# followLineMain.net
KiCad netlist of a schematic drawn in EAGLE
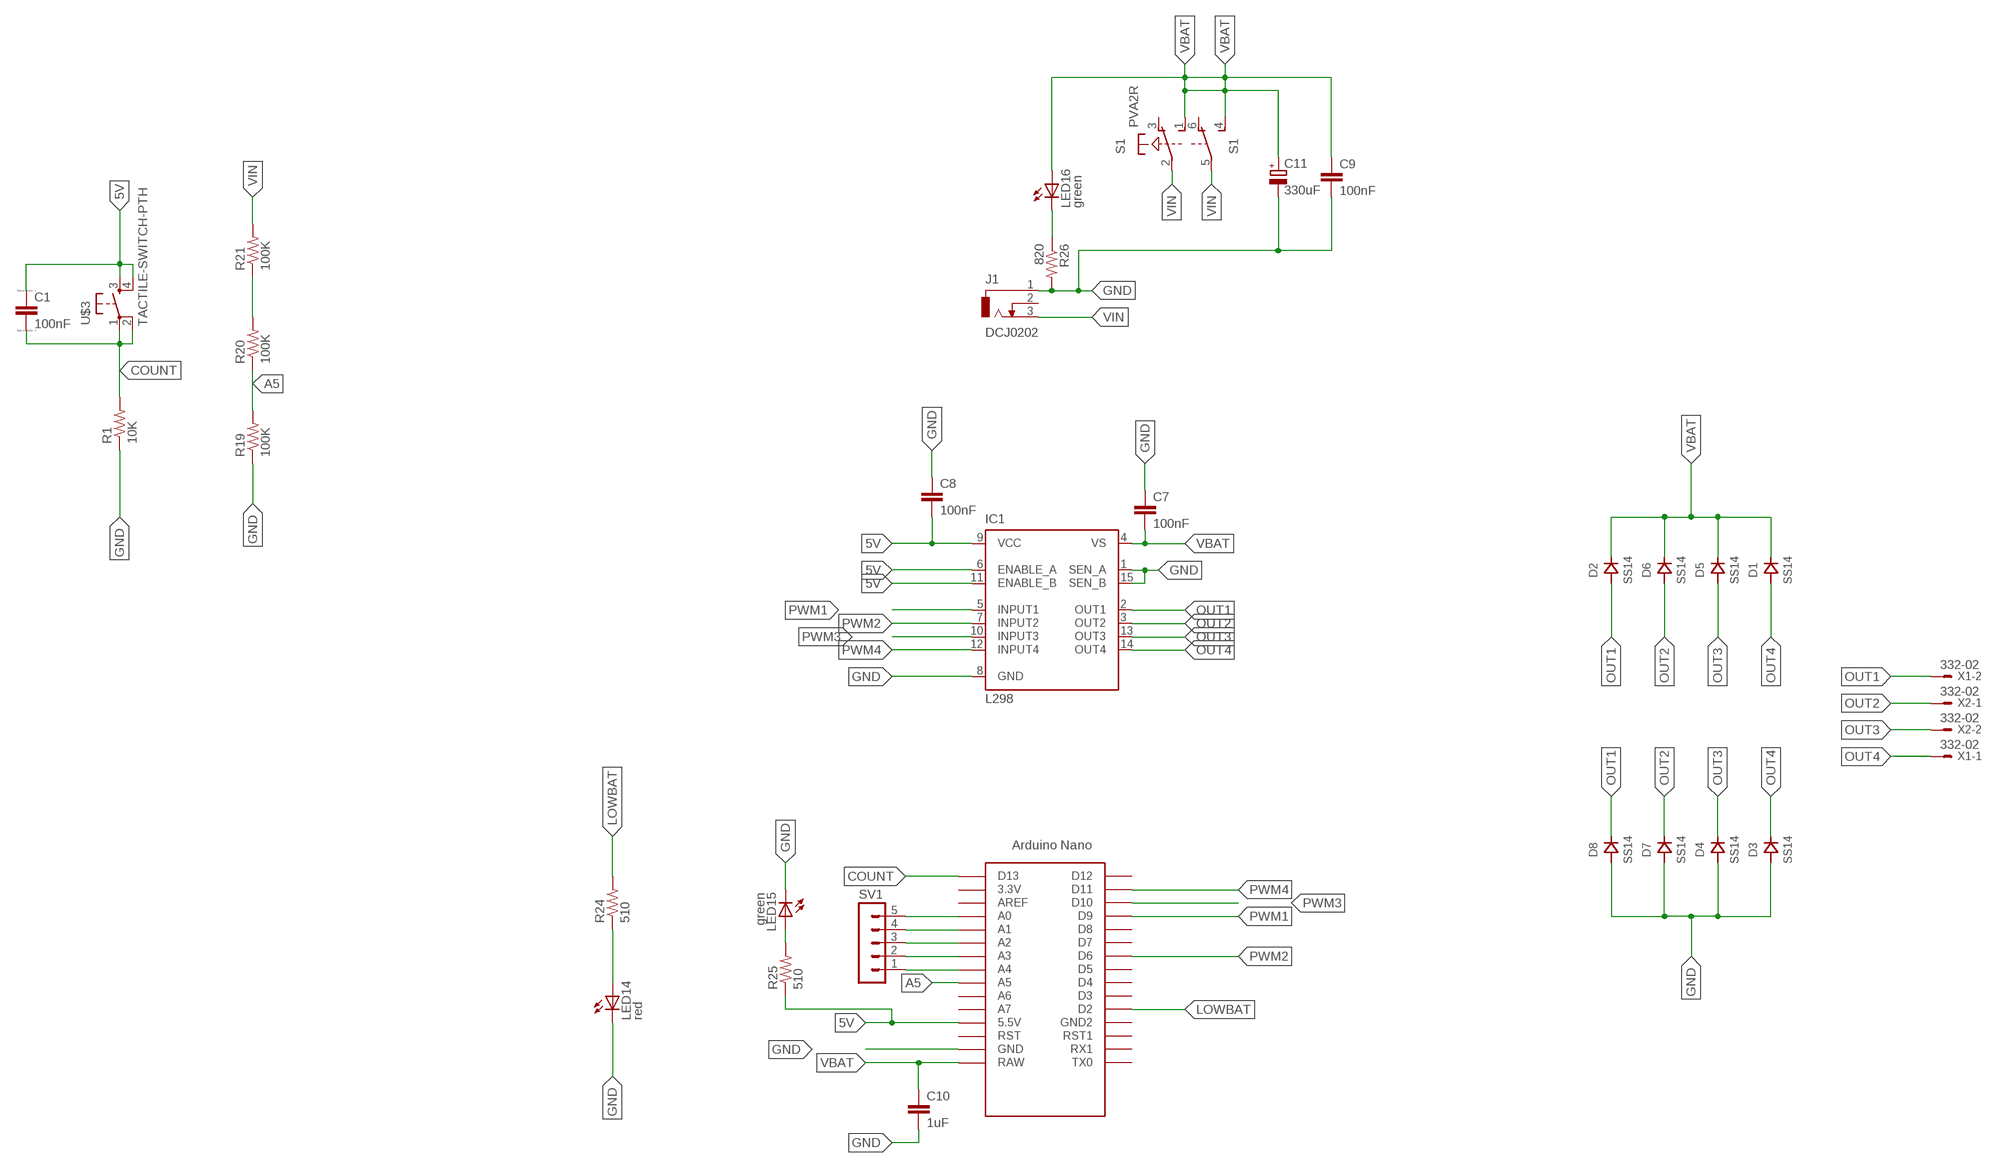
[diagram p0: schematic, sheet 1]

(export (version "E")
  (design (tool "Eeschema 10.0.6"))
  (components
    (comp (ref "C1")
      (value "100nF")
      (footprint "eagle-import:C0603")
      (libsource (lib "eagle-import") (part "CC0603"))
    )
    (comp (ref "C7")
      (value "100nF")
      (footprint "eagle-import:0805")
      (libsource (lib "eagle-import") (part "CAP0805"))
    )
    (comp (ref "C8")
      (value "100nF")
      (footprint "eagle-import:0805")
      (libsource (lib "eagle-import") (part "CAP0805"))
    )
    (comp (ref "C9")
      (value "100nF")
      (footprint "eagle-import:0805")
      (libsource (lib "eagle-import") (part "CAP0805"))
    )
    (comp (ref "C10")
      (value "1uF")
      (footprint "eagle-import:1206")
      (libsource (lib "eagle-import") (part "CAP1206"))
    )
    (comp (ref "C11")
      (value "330uF")
      (footprint "eagle-import:E5-13")
      (libsource (lib "eagle-import") (part "CPOL-EUE5-13"))
    )
    (comp (ref "D1")
      (value "SS14")
      (footprint "eagle-import:DO214")
      (libsource (lib "eagle-import") (part "SS14"))
    )
    (comp (ref "D2")
      (value "SS14")
      (footprint "eagle-import:DO214")
      (libsource (lib "eagle-import") (part "SS14"))
    )
    (comp (ref "D3")
      (value "SS14")
      (footprint "eagle-import:DO214")
      (libsource (lib "eagle-import") (part "SS14"))
    )
    (comp (ref "D4")
      (value "SS14")
      (footprint "eagle-import:DO214")
      (libsource (lib "eagle-import") (part "SS14"))
    )
    (comp (ref "D5")
      (value "SS14")
      (footprint "eagle-import:DO214")
      (libsource (lib "eagle-import") (part "SS14"))
    )
    (comp (ref "D6")
      (value "SS14")
      (footprint "eagle-import:DO214")
      (libsource (lib "eagle-import") (part "SS14"))
    )
    (comp (ref "D7")
      (value "SS14")
      (footprint "eagle-import:DO214")
      (libsource (lib "eagle-import") (part "SS14"))
    )
    (comp (ref "D8")
      (value "SS14")
      (footprint "eagle-import:DO214")
      (libsource (lib "eagle-import") (part "SS14"))
    )
    (comp (ref "IC1")
      (value "L298")
      (footprint "eagle-import:MULTIWATT-15")
      (fields (field (name "MPN") "L298N"))
      (libsource (lib "eagle-import") (part "L298"))
    )
    (comp (ref "J1")
      (value "DCJ0202")
      (footprint "eagle-import:DCJ0202")
      (libsource (lib "eagle-import") (part "DCJ0202"))
    )
    (comp (ref "LED14")
      (value "red")
      (footprint "eagle-import:SML0805")
      (libsource (lib "eagle-import") (part "LEDSML0805"))
    )
    (comp (ref "LED15")
      (value "green")
      (footprint "eagle-import:SML0805")
      (libsource (lib "eagle-import") (part "LEDSML0805"))
    )
    (comp (ref "LED16")
      (value "green")
      (footprint "eagle-import:SML0805")
      (libsource (lib "eagle-import") (part "LEDSML0805"))
    )
    (comp (ref "R1")
      (value "10K")
      (footprint "eagle-import:0805")
      (libsource (lib "eagle-import") (part "RESISTOR0805-RES"))
    )
    (comp (ref "R19")
      (value "100K")
      (footprint "eagle-import:0805")
      (libsource (lib "eagle-import") (part "RESISTOR0805-RES"))
    )
    (comp (ref "R20")
      (value "100K")
      (footprint "eagle-import:0805")
      (libsource (lib "eagle-import") (part "RESISTOR0805-RES"))
    )
    (comp (ref "R21")
      (value "100K")
      (footprint "eagle-import:0805")
      (libsource (lib "eagle-import") (part "RESISTOR0805-RES"))
    )
    (comp (ref "R24")
      (value "510")
      (footprint "eagle-import:0805")
      (libsource (lib "eagle-import") (part "RESISTOR0805-RES"))
    )
    (comp (ref "R25")
      (value "510")
      (footprint "eagle-import:0805")
      (libsource (lib "eagle-import") (part "RESISTOR0805-RES"))
    )
    (comp (ref "R26")
      (value "820")
      (footprint "eagle-import:0805")
      (libsource (lib "eagle-import") (part "RESISTOR0805-RES"))
    )
    (comp (ref "S1")
      (value "PVA2R")
      (footprint "eagle-import:PVA2R")
      (libsource (lib "eagle-import") (part "PVA2R"))
    )
    (comp (ref "SV1")
      (value "MA05-1")
      (footprint "eagle-import:MA05-1")
      (libsource (lib "eagle-import") (part "MA05-1"))
    )
    (comp (ref "U$1")
      (value "NANO")
      (footprint "eagle-import:NANO")
      (libsource (lib "eagle-import") (part "NANO"))
    )
    (comp (ref "U$3")
      (value "TACTILE-SWITCH-PTH")
      (footprint "eagle-import:TAC-SWITCH-PTH")
      (libsource (lib "eagle-import") (part "TACTILE-SWITCH-PTH"))
    )
    (comp (ref "X1")
      (value "332-02")
      (footprint "eagle-import:332-02")
      (libsource (lib "eagle-import") (part "332-02"))
    )
    (comp (ref "X2")
      (value "332-02")
      (footprint "eagle-import:332-02")
      (libsource (lib "eagle-import") (part "332-02"))
    )
  )
  (nets
    (net (code "1") (name "5V") (class "Default")
      (node (ref "C1") (pin "1") (pinfunction "1_1") (pintype "passive"))
      (node (ref "C8") (pin "2") (pinfunction "2_2") (pintype "passive"))
      (node (ref "IC1") (pin "11") (pinfunction "ENABLE_B_11") (pintype "input"))
      (node (ref "IC1") (pin "6") (pinfunction "ENABLE_A_6") (pintype "input"))
      (node (ref "IC1") (pin "9") (pinfunction "VCC_9") (pintype "power_in"))
      (node (ref "R25") (pin "1") (pinfunction "1_1") (pintype "passive"))
      (node (ref "U$1") (pin "5V") (pinfunction "5.5V_5V") (pintype "bidirectional"))
      (node (ref "U$3") (pin "3") (pinfunction "3_3") (pintype "passive"))
      (node (ref "U$3") (pin "4") (pinfunction "4_4") (pintype "passive"))
    )
    (net (code "2") (name "A5") (class "Default")
      (node (ref "R19") (pin "2") (pinfunction "2_2") (pintype "passive"))
      (node (ref "R20") (pin "1") (pinfunction "1_1") (pintype "passive"))
      (node (ref "U$1") (pin "A5") (pinfunction "A5_A5") (pintype "bidirectional"))
    )
    (net (code "3") (name "COUNT") (class "Default")
      (node (ref "C1") (pin "2") (pinfunction "2_2") (pintype "passive"))
      (node (ref "R1") (pin "2") (pinfunction "2_2") (pintype "passive"))
      (node (ref "U$1") (pin "D13") (pinfunction "D13_D13") (pintype "bidirectional"))
      (node (ref "U$3") (pin "1") (pinfunction "1_1") (pintype "passive"))
      (node (ref "U$3") (pin "2") (pinfunction "2_2") (pintype "passive"))
    )
    (net (code "4") (name "GND") (class "Default")
      (node (ref "C10") (pin "2") (pinfunction "2_2") (pintype "passive"))
      (node (ref "C11") (pin "-") (pinfunction "-_-") (pintype "passive"))
      (node (ref "C7") (pin "1") (pinfunction "1_1") (pintype "passive"))
      (node (ref "C8") (pin "1") (pinfunction "1_1") (pintype "passive"))
      (node (ref "C9") (pin "2") (pinfunction "2_2") (pintype "passive"))
      (node (ref "D3") (pin "ANODE") (pinfunction "ANODE_ANODE") (pintype "bidirectional"))
      (node (ref "D4") (pin "ANODE") (pinfunction "ANODE_ANODE") (pintype "bidirectional"))
      (node (ref "D7") (pin "ANODE") (pinfunction "ANODE_ANODE") (pintype "bidirectional"))
      (node (ref "D8") (pin "ANODE") (pinfunction "ANODE_ANODE") (pintype "bidirectional"))
      (node (ref "IC1") (pin "1") (pinfunction "SEN_A_1") (pintype "input"))
      (node (ref "IC1") (pin "15") (pinfunction "SEN_B_15") (pintype "input"))
      (node (ref "IC1") (pin "8") (pinfunction "GND_8") (pintype "power_in"))
      (node (ref "J1") (pin "1") (pinfunction "1_1") (pintype "passive"))
      (node (ref "LED14") (pin "C") (pinfunction "C_C") (pintype "passive"))
      (node (ref "LED15") (pin "C") (pinfunction "C_C") (pintype "passive"))
      (node (ref "R1") (pin "1") (pinfunction "1_1") (pintype "passive"))
      (node (ref "R19") (pin "1") (pinfunction "1_1") (pintype "passive"))
      (node (ref "R26") (pin "2") (pinfunction "2_2") (pintype "passive"))
      (node (ref "U$1") (pin "GND") (pinfunction "GND_GND") (pintype "bidirectional"))
    )
    (net (code "5") (name "LOWBAT") (class "Default")
      (node (ref "R24") (pin "2") (pinfunction "2_2") (pintype "passive"))
      (node (ref "U$1") (pin "D2") (pinfunction "D2_D2") (pintype "bidirectional"))
    )
    (net (code "6") (name "Net-(LED14-PadA)") (class "Default")
      (node (ref "LED14") (pin "A") (pinfunction "A_A") (pintype "passive"))
      (node (ref "R24") (pin "1") (pinfunction "1_1") (pintype "passive"))
    )
    (net (code "7") (name "Net-(LED15-PadA)") (class "Default")
      (node (ref "LED15") (pin "A") (pinfunction "A_A") (pintype "passive"))
      (node (ref "R25") (pin "2") (pinfunction "2_2") (pintype "passive"))
    )
    (net (code "8") (name "Net-(LED16-PadC)") (class "Default")
      (node (ref "LED16") (pin "C") (pinfunction "C_C") (pintype "passive"))
      (node (ref "R26") (pin "1") (pinfunction "1_1") (pintype "passive"))
    )
    (net (code "9") (name "Net-(R20-Pad2)") (class "Default")
      (node (ref "R20") (pin "2") (pinfunction "2_2") (pintype "passive"))
      (node (ref "R21") (pin "1") (pinfunction "1_1") (pintype "passive"))
    )
    (net (code "10") (name "Net-(SV1-Pad1)") (class "Default")
      (node (ref "SV1") (pin "1") (pinfunction "1_1") (pintype "passive"))
      (node (ref "U$1") (pin "A4") (pinfunction "A4_A4") (pintype "bidirectional"))
    )
    (net (code "11") (name "Net-(SV1-Pad2)") (class "Default")
      (node (ref "SV1") (pin "2") (pinfunction "2_2") (pintype "passive"))
      (node (ref "U$1") (pin "A3") (pinfunction "A3_A3") (pintype "bidirectional"))
    )
    (net (code "12") (name "Net-(SV1-Pad3)") (class "Default")
      (node (ref "SV1") (pin "3") (pinfunction "3_3") (pintype "passive"))
      (node (ref "U$1") (pin "A2") (pinfunction "A2_A2") (pintype "bidirectional"))
    )
    (net (code "13") (name "Net-(SV1-Pad4)") (class "Default")
      (node (ref "SV1") (pin "4") (pinfunction "4_4") (pintype "passive"))
      (node (ref "U$1") (pin "A1") (pinfunction "A1_A1") (pintype "bidirectional"))
    )
    (net (code "14") (name "Net-(SV1-Pad5)") (class "Default")
      (node (ref "SV1") (pin "5") (pinfunction "5_5") (pintype "passive"))
      (node (ref "U$1") (pin "A0") (pinfunction "A0_A0") (pintype "bidirectional"))
    )
    (net (code "15") (name "OUT1") (class "Default")
      (node (ref "D2") (pin "ANODE") (pinfunction "ANODE_ANODE") (pintype "bidirectional"))
      (node (ref "D8") (pin "CATHODE") (pinfunction "CATHODE_CATHODE") (pintype "bidirectional"))
      (node (ref "IC1") (pin "2") (pinfunction "OUT1_2") (pintype "output"))
      (node (ref "X1") (pin "2") (pinfunction "S_2") (pintype "passive"))
    )
    (net (code "16") (name "OUT2") (class "Default")
      (node (ref "D6") (pin "ANODE") (pinfunction "ANODE_ANODE") (pintype "bidirectional"))
      (node (ref "D7") (pin "CATHODE") (pinfunction "CATHODE_CATHODE") (pintype "bidirectional"))
      (node (ref "IC1") (pin "3") (pinfunction "OUT2_3") (pintype "output"))
      (node (ref "X2") (pin "1") (pinfunction "S_1") (pintype "passive"))
    )
    (net (code "17") (name "OUT3") (class "Default")
      (node (ref "D4") (pin "CATHODE") (pinfunction "CATHODE_CATHODE") (pintype "bidirectional"))
      (node (ref "D5") (pin "ANODE") (pinfunction "ANODE_ANODE") (pintype "bidirectional"))
      (node (ref "IC1") (pin "13") (pinfunction "OUT3_13") (pintype "output"))
      (node (ref "X2") (pin "2") (pinfunction "S_2") (pintype "passive"))
    )
    (net (code "18") (name "OUT4") (class "Default")
      (node (ref "D1") (pin "ANODE") (pinfunction "ANODE_ANODE") (pintype "bidirectional"))
      (node (ref "D3") (pin "CATHODE") (pinfunction "CATHODE_CATHODE") (pintype "bidirectional"))
      (node (ref "IC1") (pin "14") (pinfunction "OUT4_14") (pintype "output"))
      (node (ref "X1") (pin "1") (pinfunction "S_1") (pintype "passive"))
    )
    (net (code "19") (name "PWM1") (class "Default")
      (node (ref "IC1") (pin "5") (pinfunction "INPUT1_5") (pintype "input"))
      (node (ref "U$1") (pin "D9") (pinfunction "D9_D9") (pintype "bidirectional"))
    )
    (net (code "20") (name "PWM2") (class "Default")
      (node (ref "IC1") (pin "7") (pinfunction "INPUT2_7") (pintype "input"))
      (node (ref "U$1") (pin "D6") (pinfunction "D6_D6") (pintype "bidirectional"))
    )
    (net (code "21") (name "PWM3") (class "Default")
      (node (ref "IC1") (pin "10") (pinfunction "INPUT3_10") (pintype "input"))
      (node (ref "U$1") (pin "D10") (pinfunction "D10_D10") (pintype "bidirectional"))
    )
    (net (code "22") (name "PWM4") (class "Default")
      (node (ref "IC1") (pin "12") (pinfunction "INPUT4_12") (pintype "input"))
      (node (ref "U$1") (pin "D11") (pinfunction "D11_D11") (pintype "bidirectional"))
    )
    (net (code "23") (name "VBAT") (class "Default")
      (node (ref "C10") (pin "1") (pinfunction "1_1") (pintype "passive"))
      (node (ref "C11") (pin "+") (pinfunction "+_+") (pintype "passive"))
      (node (ref "C7") (pin "2") (pinfunction "2_2") (pintype "passive"))
      (node (ref "C9") (pin "1") (pinfunction "1_1") (pintype "passive"))
      (node (ref "D1") (pin "CATHODE") (pinfunction "CATHODE_CATHODE") (pintype "bidirectional"))
      (node (ref "D2") (pin "CATHODE") (pinfunction "CATHODE_CATHODE") (pintype "bidirectional"))
      (node (ref "D5") (pin "CATHODE") (pinfunction "CATHODE_CATHODE") (pintype "bidirectional"))
      (node (ref "D6") (pin "CATHODE") (pinfunction "CATHODE_CATHODE") (pintype "bidirectional"))
      (node (ref "IC1") (pin "4") (pinfunction "VS_4") (pintype "power_in"))
      (node (ref "LED16") (pin "A") (pinfunction "A_A") (pintype "passive"))
      (node (ref "S1") (pin "1") (pinfunction "S_1") (pintype "passive"))
      (node (ref "S1") (pin "4") (pinfunction "S_4") (pintype "passive"))
      (node (ref "U$1") (pin "RAW") (pinfunction "RAW_RAW") (pintype "bidirectional"))
    )
    (net (code "24") (name "VIN") (class "Default")
      (node (ref "J1") (pin "3") (pinfunction "3_3") (pintype "passive"))
      (node (ref "R21") (pin "2") (pinfunction "2_2") (pintype "passive"))
      (node (ref "S1") (pin "2") (pinfunction "P_2") (pintype "passive"))
      (node (ref "S1") (pin "5") (pinfunction "P_5") (pintype "passive"))
    )
    (net (code "25") (name "unconnected-(J1-Pad2)") (class "Default")
      (node (ref "J1") (pin "2") (pinfunction "2_2") (pintype "passive"))
    )
    (net (code "26") (name "unconnected-(S1A-O-Pad3)") (class "Default")
      (node (ref "S1") (pin "3") (pinfunction "O_3") (pintype "passive"))
    )
    (net (code "27") (name "unconnected-(S1B-O-Pad6)") (class "Default")
      (node (ref "S1") (pin "6") (pinfunction "O_6") (pintype "passive"))
    )
    (net (code "28") (name "unconnected-(U$1-GND2-PadGND1)") (class "Default")
      (node (ref "U$1") (pin "GND1") (pinfunction "GND2_GND1") (pintype "bidirectional"))
    )
    (net (code "29") (name "unconnected-(U$1-Pad3.3V)") (class "Default")
      (node (ref "U$1") (pin "3.3V") (pinfunction "3.3V_3.3V") (pintype "bidirectional"))
    )
    (net (code "30") (name "unconnected-(U$1-PadA6)") (class "Default")
      (node (ref "U$1") (pin "A6") (pinfunction "A6_A6") (pintype "bidirectional"))
    )
    (net (code "31") (name "unconnected-(U$1-PadA7)") (class "Default")
      (node (ref "U$1") (pin "A7") (pinfunction "A7_A7") (pintype "bidirectional"))
    )
    (net (code "32") (name "unconnected-(U$1-PadAREF)") (class "Default")
      (node (ref "U$1") (pin "AREF") (pinfunction "AREF_AREF") (pintype "bidirectional"))
    )
    (net (code "33") (name "unconnected-(U$1-PadD3)") (class "Default")
      (node (ref "U$1") (pin "D3") (pinfunction "D3_D3") (pintype "bidirectional"))
    )
    (net (code "34") (name "unconnected-(U$1-PadD4)") (class "Default")
      (node (ref "U$1") (pin "D4") (pinfunction "D4_D4") (pintype "bidirectional"))
    )
    (net (code "35") (name "unconnected-(U$1-PadD5)") (class "Default")
      (node (ref "U$1") (pin "D5") (pinfunction "D5_D5") (pintype "bidirectional"))
    )
    (net (code "36") (name "unconnected-(U$1-PadD7)") (class "Default")
      (node (ref "U$1") (pin "D7") (pinfunction "D7_D7") (pintype "bidirectional"))
    )
    (net (code "37") (name "unconnected-(U$1-PadD8)") (class "Default")
      (node (ref "U$1") (pin "D8") (pinfunction "D8_D8") (pintype "bidirectional"))
    )
    (net (code "38") (name "unconnected-(U$1-PadD12)") (class "Default")
      (node (ref "U$1") (pin "D12") (pinfunction "D12_D12") (pintype "bidirectional"))
    )
    (net (code "39") (name "unconnected-(U$1-PadICSP1)") (class "Default")
      (node (ref "U$1") (pin "ICSP1") (pinfunction "ICSP1_ICSP1") (pintype "bidirectional"))
    )
    (net (code "40") (name "unconnected-(U$1-PadICSP2)") (class "Default")
      (node (ref "U$1") (pin "ICSP2") (pinfunction "ICSP2_ICSP2") (pintype "bidirectional"))
    )
    (net (code "41") (name "unconnected-(U$1-PadICSP3)") (class "Default")
      (node (ref "U$1") (pin "ICSP3") (pinfunction "ICSP3_ICSP3") (pintype "bidirectional"))
    )
    (net (code "42") (name "unconnected-(U$1-PadICSP4)") (class "Default")
      (node (ref "U$1") (pin "ICSP4") (pinfunction "ICSP4_ICSP4") (pintype "bidirectional"))
    )
    (net (code "43") (name "unconnected-(U$1-PadICSP5)") (class "Default")
      (node (ref "U$1") (pin "ICSP5") (pinfunction "ICSP5_ICSP5") (pintype "bidirectional"))
    )
    (net (code "44") (name "unconnected-(U$1-PadICSP6)") (class "Default")
      (node (ref "U$1") (pin "ICSP6") (pinfunction "ICSP6_ICSP6") (pintype "bidirectional"))
    )
    (net (code "45") (name "unconnected-(U$1-PadRST)") (class "Default")
      (node (ref "U$1") (pin "RST") (pinfunction "RST_RST") (pintype "bidirectional"))
    )
    (net (code "46") (name "unconnected-(U$1-PadRST1)") (class "Default")
      (node (ref "U$1") (pin "RST1") (pinfunction "RST1_RST1") (pintype "bidirectional"))
    )
    (net (code "47") (name "unconnected-(U$1-PadRX1)") (class "Default")
      (node (ref "U$1") (pin "RX1") (pinfunction "RX1_RX1") (pintype "bidirectional"))
    )
    (net (code "48") (name "unconnected-(U$1-PadTX0)") (class "Default")
      (node (ref "U$1") (pin "TX0") (pinfunction "TX0_TX0") (pintype "bidirectional"))
    )
  )
)
